# IR_Reciever.net
KiCad netlist of a schematic drawn in Altium Designer
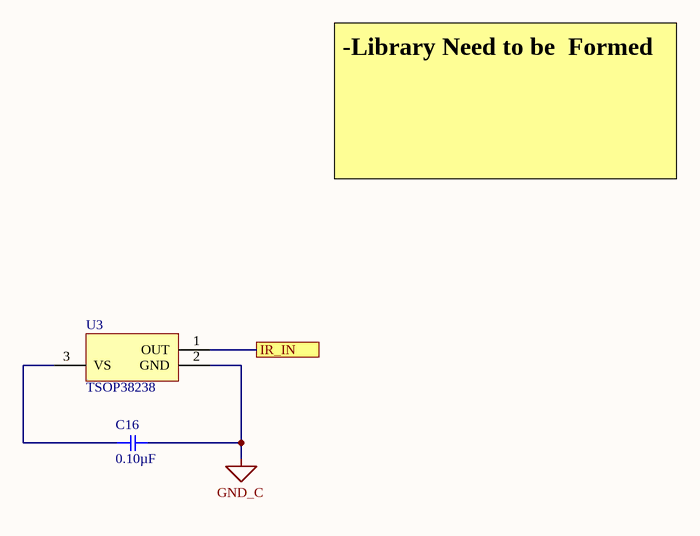
[diagram p0: IR_Reciever.SchDoc]

(export (version "E")
  (design (tool "Eeschema 10.0.6"))
  (components
    (comp (ref "C16")
      (value "0.10µF")
      (footprint "SMD-0805C")
      (description "CAP CER 0.1UF 50V X7R 0805")
      (fields
        (field (name "DIGI-KEY PART NUMBER") "490-9754-1-ND")
        (field (name "PART NUMBER") "GRM21BR71H104KA01K")
      )
      (libsource (lib "capacitor_murata_0805") (part "GRM21BR71H104KA01K"))
    )
    (comp (ref "U3")
      (value "TSOP38238")
      (footprint "VISH-TSOP38238")
      (description "IR Receiver Modules for Remote Control System, 2.5 to 5.5 V, -25 to 85 degC, 3-Pin THD, RoHS, Bulk")
      (fields (field (name "TOLERANCE") "30ppm"))
      (libsource (lib "Edge_Card_Ucc28951") (part "CMP-1666-00022-1"))
    )
  )
  (nets
    (net (code "1") (name "/IR_IN") (class "Default")
      (node (ref "U3") (pin "1") (pinfunction "OUT_1") (pintype "power_in"))
    )
    (net (code "2") (name "GND_C") (class "Default")
      (node (ref "C16") (pin "2") (pinfunction "2_2") (pintype "passive"))
      (node (ref "U3") (pin "2") (pinfunction "GND_2") (pintype "power_in"))
    )
    (net (code "3") (name "Net-(U3-VS)") (class "Default")
      (node (ref "C16") (pin "1") (pinfunction "1_1") (pintype "passive"))
      (node (ref "U3") (pin "3") (pinfunction "VS_3") (pintype "power_in"))
    )
  )
)
